# linearSensor.net
KiCad netlist of a schematic drawn in EAGLE
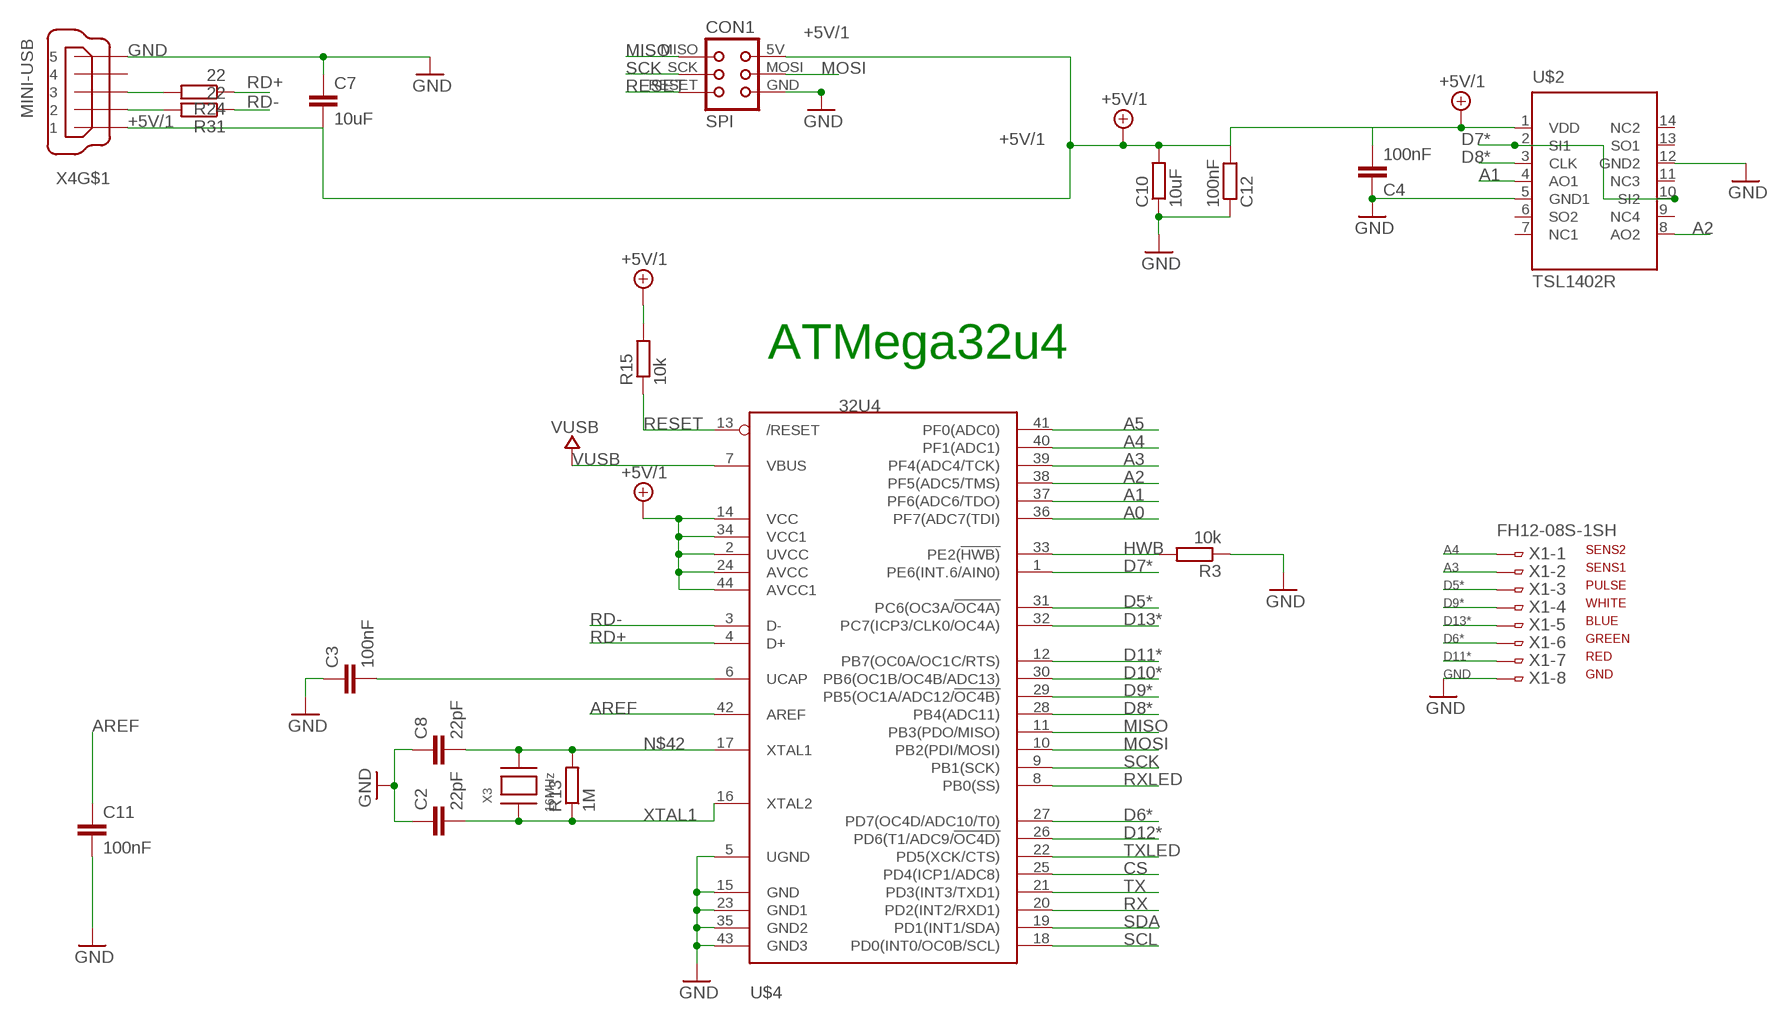
[diagram p0: schematic, sheet 1]

(export (version "E")
  (design (tool "Eeschema 10.0.6"))
  (components
    (comp (ref "C2")
      (value "22pF")
      (footprint "eagle-import:C0805K")
      (libsource (lib "eagle-import") (part "C-EUC0805K"))
    )
    (comp (ref "C3")
      (value "100nF")
      (footprint "eagle-import:C0805K")
      (libsource (lib "eagle-import") (part "C-EUC0805K"))
    )
    (comp (ref "C4")
      (value "100nF")
      (footprint "eagle-import:C0805")
      (libsource (lib "eagle-import") (part "C-EUC0805"))
    )
    (comp (ref "C7")
      (value "10uF")
      (footprint "eagle-import:C0805")
      (libsource (lib "eagle-import") (part "C-EUC0805"))
    )
    (comp (ref "C8")
      (value "22pF")
      (footprint "eagle-import:C0805K")
      (libsource (lib "eagle-import") (part "C-EUC0805K"))
    )
    (comp (ref "C10")
      (value "10uF")
      (footprint "eagle-import:M0805")
      (libsource (lib "eagle-import") (part "R-EU_M0805"))
    )
    (comp (ref "C11")
      (value "100nF")
      (footprint "eagle-import:C0805K")
      (libsource (lib "eagle-import") (part "C-EUC0805K"))
    )
    (comp (ref "C12")
      (value "100nF")
      (footprint "eagle-import:M0805")
      (libsource (lib "eagle-import") (part "R-EU_M0805"))
    )
    (comp (ref "CON1")
      (value "SPI")
      (footprint "eagle-import:TC2030-MCP-NL")
      (libsource (lib "eagle-import") (part "TINYISPT"))
    )
    (comp (ref "R3")
      (value "10k")
      (footprint "eagle-import:M0805")
      (libsource (lib "eagle-import") (part "resistor_R-EU_M0805"))
    )
    (comp (ref "R13")
      (value "1M")
      (footprint "eagle-import:M0805")
      (libsource (lib "eagle-import") (part "R-EU_M0805"))
    )
    (comp (ref "R15")
      (value "10k")
      (footprint "eagle-import:M0805")
      (libsource (lib "eagle-import") (part "resistor_R-EU_M0805"))
    )
    (comp (ref "R24")
      (value "22")
      (footprint "eagle-import:M0805")
      (libsource (lib "eagle-import") (part "R-EU_M0805"))
    )
    (comp (ref "R31")
      (value "22")
      (footprint "eagle-import:M0805")
      (libsource (lib "eagle-import") (part "R-EU_M0805"))
    )
    (comp (ref "U$2")
      (value "TSL1402R")
      (footprint "eagle-import:DIL14")
      (libsource (lib "eagle-import") (part "TSL1402R"))
    )
    (comp (ref "U$4")
      (value "32U4")
      (footprint "eagle-import:TQFP44")
      (libsource (lib "eagle-import") (part "ATMEGA32U4-AU"))
    )
    (comp (ref "X1")
      (value "FH12-08S-1SH")
      (footprint "eagle-import:FH12-08S-1SH")
      (libsource (lib "eagle-import") (part "FH12-08S-1SH"))
    )
    (comp (ref "X3")
      (value "16MHz")
      (footprint "eagle-import:NX6035")
      (libsource (lib "eagle-import") (part "XTALNX6035"))
    )
    (comp (ref "X4")
      (value "MINI-USB")
      (footprint "eagle-import:32005-201")
      (libsource (lib "eagle-import") (part "MINI-USB-SCHIELD-32005-201"))
    )
  )
  (nets
    (net (code "1") (name "+5V{slash}1") (class "Default")
      (node (ref "C10") (pin "2") (pinfunction "2_2") (pintype "passive"))
      (node (ref "C12") (pin "2") (pinfunction "2_2") (pintype "passive"))
      (node (ref "C4") (pin "2") (pinfunction "2_2") (pintype "passive"))
      (node (ref "C7") (pin "2") (pinfunction "2_2") (pintype "passive"))
      (node (ref "CON1") (pin "5V") (pinfunction "VCC_5V") (pintype "passive"))
      (node (ref "R15") (pin "2") (pinfunction "2_2") (pintype "passive"))
      (node (ref "U$2") (pin "1") (pinfunction "VDD_1") (pintype "power_in"))
      (node (ref "U$4") (pin "14") (pinfunction "VCC_14") (pintype "bidirectional"))
      (node (ref "U$4") (pin "2") (pinfunction "UVCC_2") (pintype "bidirectional"))
      (node (ref "U$4") (pin "24") (pinfunction "AVCC_24") (pintype "bidirectional"))
      (node (ref "U$4") (pin "34") (pinfunction "VCC1_34") (pintype "bidirectional"))
      (node (ref "U$4") (pin "44") (pinfunction "AVCC1_44") (pintype "bidirectional"))
      (node (ref "X4") (pin "1") (pinfunction "1_1") (pintype "passive"))
    )
    (net (code "2") (name "/A0") (class "Default")
      (node (ref "U$4") (pin "36") (pinfunction "PF7(ADC7(TDI)_36") (pintype "bidirectional"))
    )
    (net (code "3") (name "/A1") (class "Default")
      (node (ref "U$2") (pin "4") (pinfunction "AO1_4") (pintype "output"))
      (node (ref "U$4") (pin "37") (pinfunction "PF6(ADC6/TDO)_37") (pintype "bidirectional"))
    )
    (net (code "4") (name "/A2") (class "Default")
      (node (ref "U$2") (pin "8") (pinfunction "AO2_8") (pintype "output"))
      (node (ref "U$4") (pin "38") (pinfunction "PF5(ADC5/TMS)_38") (pintype "bidirectional"))
    )
    (net (code "5") (name "/A3") (class "Default")
      (node (ref "U$4") (pin "39") (pinfunction "PF4(ADC4/TCK)_39") (pintype "bidirectional"))
      (node (ref "X1") (pin "2") (pinfunction "1_2") (pintype "passive"))
    )
    (net (code "6") (name "/A4") (class "Default")
      (node (ref "U$4") (pin "40") (pinfunction "PF1(ADC1)_40") (pintype "bidirectional"))
      (node (ref "X1") (pin "1") (pinfunction "1_1") (pintype "passive"))
    )
    (net (code "7") (name "/A5") (class "Default")
      (node (ref "U$4") (pin "41") (pinfunction "PF0(ADC0)_41") (pintype "bidirectional"))
    )
    (net (code "8") (name "/AREF") (class "Default")
      (node (ref "C11") (pin "1") (pinfunction "1_1") (pintype "passive"))
      (node (ref "U$4") (pin "42") (pinfunction "AREF_42") (pintype "bidirectional"))
    )
    (net (code "9") (name "/CS") (class "Default")
      (node (ref "U$4") (pin "25") (pinfunction "PD4(ICP1/ADC8)_25") (pintype "bidirectional"))
    )
    (net (code "10") (name "/D5*") (class "Default")
      (node (ref "U$4") (pin "31") (pinfunction "PC6(OC3A/~{OC4A})_31") (pintype "bidirectional"))
      (node (ref "X1") (pin "3") (pinfunction "1_3") (pintype "passive"))
    )
    (net (code "11") (name "/D6*") (class "Default")
      (node (ref "U$4") (pin "27") (pinfunction "PD7(OC4D/ADC10/T0)_27") (pintype "bidirectional"))
      (node (ref "X1") (pin "6") (pinfunction "1_6") (pintype "passive"))
    )
    (net (code "12") (name "/D7*") (class "Default")
      (node (ref "U$2") (pin "10") (pinfunction "SI2_10") (pintype "input"))
      (node (ref "U$2") (pin "2") (pinfunction "SI1_2") (pintype "input"))
      (node (ref "U$4") (pin "1") (pinfunction "PE6(INT.6/AIN0)_1") (pintype "bidirectional"))
    )
    (net (code "13") (name "/D8*") (class "Default")
      (node (ref "U$2") (pin "3") (pinfunction "CLK_3") (pintype "input"))
      (node (ref "U$4") (pin "28") (pinfunction "PB4(ADC11)_28") (pintype "bidirectional"))
    )
    (net (code "14") (name "/D9*") (class "Default")
      (node (ref "U$4") (pin "29") (pinfunction "PB5(OC1A/ADC12/~{OC4B})_29") (pintype "bidirectional"))
      (node (ref "X1") (pin "4") (pinfunction "1_4") (pintype "passive"))
    )
    (net (code "15") (name "/D10*") (class "Default")
      (node (ref "U$4") (pin "30") (pinfunction "PB6(OC1B/OC4B/ADC13)_30") (pintype "bidirectional"))
    )
    (net (code "16") (name "/D11*") (class "Default")
      (node (ref "U$4") (pin "12") (pinfunction "PB7(OC0A/OC1C/RTS)_12") (pintype "bidirectional"))
      (node (ref "X1") (pin "7") (pinfunction "1_7") (pintype "passive"))
    )
    (net (code "17") (name "/D12*") (class "Default")
      (node (ref "U$4") (pin "26") (pinfunction "PD6(T1/ADC9/~{OC4D})_26") (pintype "bidirectional"))
    )
    (net (code "18") (name "/D13*") (class "Default")
      (node (ref "U$4") (pin "32") (pinfunction "PC7(ICP3/CLK0/OC4A)_32") (pintype "bidirectional"))
      (node (ref "X1") (pin "5") (pinfunction "1_5") (pintype "passive"))
    )
    (net (code "19") (name "/HWB") (class "Default")
      (node (ref "R3") (pin "2") (pinfunction "2_2") (pintype "passive"))
      (node (ref "U$4") (pin "33") (pinfunction "PE2(~{HWB})_33") (pintype "bidirectional"))
    )
    (net (code "20") (name "/MISO") (class "Default")
      (node (ref "CON1") (pin "MISO") (pinfunction "MISO_MISO") (pintype "passive"))
      (node (ref "U$4") (pin "11") (pinfunction "PB3(PDO/MISO)_11") (pintype "bidirectional"))
    )
    (net (code "21") (name "/MOSI") (class "Default")
      (node (ref "CON1") (pin "MOSI") (pinfunction "MOSI_MOSI") (pintype "passive"))
      (node (ref "U$4") (pin "10") (pinfunction "PB2(PDI/MOSI)_10") (pintype "bidirectional"))
    )
    (net (code "22") (name "/N$42") (class "Default")
      (node (ref "C8") (pin "2") (pinfunction "2_2") (pintype "passive"))
      (node (ref "R13") (pin "2") (pinfunction "2_2") (pintype "passive"))
      (node (ref "U$4") (pin "17") (pinfunction "XTAL1_17") (pintype "bidirectional"))
      (node (ref "X3") (pin "P$2") (pinfunction "P$2_P$2") (pintype "bidirectional"))
    )
    (net (code "23") (name "/RD+") (class "Default")
      (node (ref "R24") (pin "1") (pinfunction "1_1") (pintype "passive"))
      (node (ref "U$4") (pin "4") (pinfunction "D+_4") (pintype "bidirectional"))
    )
    (net (code "24") (name "/RD-") (class "Default")
      (node (ref "R31") (pin "1") (pinfunction "1_1") (pintype "passive"))
      (node (ref "U$4") (pin "3") (pinfunction "D-_3") (pintype "bidirectional"))
    )
    (net (code "25") (name "/RESET") (class "Default")
      (node (ref "CON1") (pin "RESET") (pinfunction "RESET_RESET") (pintype "passive"))
      (node (ref "R15") (pin "1") (pinfunction "1_1") (pintype "passive"))
      (node (ref "U$4") (pin "13") (pinfunction "/RESET_13") (pintype "bidirectional"))
    )
    (net (code "26") (name "/RX") (class "Default")
      (node (ref "U$4") (pin "20") (pinfunction "PD2(INT2/RXD1)_20") (pintype "bidirectional"))
    )
    (net (code "27") (name "/RXLED") (class "Default")
      (node (ref "U$4") (pin "8") (pinfunction "PB0(SS)_8") (pintype "bidirectional"))
    )
    (net (code "28") (name "/SCK") (class "Default")
      (node (ref "CON1") (pin "SCK") (pinfunction "SCK_SCK") (pintype "passive"))
      (node (ref "U$4") (pin "9") (pinfunction "PB1(SCK)_9") (pintype "bidirectional"))
    )
    (net (code "29") (name "/SCL") (class "Default")
      (node (ref "U$4") (pin "18") (pinfunction "PD0(INT0/OC0B/SCL)_18") (pintype "bidirectional"))
    )
    (net (code "30") (name "/SDA") (class "Default")
      (node (ref "U$4") (pin "19") (pinfunction "PD1(INT1/SDA)_19") (pintype "bidirectional"))
    )
    (net (code "31") (name "/TX") (class "Default")
      (node (ref "U$4") (pin "21") (pinfunction "PD3(INT3/TXD1)_21") (pintype "bidirectional"))
    )
    (net (code "32") (name "/TXLED") (class "Default")
      (node (ref "U$4") (pin "22") (pinfunction "PD5(XCK/CTS)_22") (pintype "bidirectional"))
    )
    (net (code "33") (name "/XTAL1") (class "Default")
      (node (ref "C2") (pin "2") (pinfunction "2_2") (pintype "passive"))
      (node (ref "R13") (pin "1") (pinfunction "1_1") (pintype "passive"))
      (node (ref "U$4") (pin "16") (pinfunction "XTAL2_16") (pintype "bidirectional"))
      (node (ref "X3") (pin "P$1") (pinfunction "P$1_P$1") (pintype "bidirectional"))
    )
    (net (code "34") (name "GND") (class "Default")
      (node (ref "C10") (pin "1") (pinfunction "1_1") (pintype "passive"))
      (node (ref "C11") (pin "2") (pinfunction "2_2") (pintype "passive"))
      (node (ref "C12") (pin "1") (pinfunction "1_1") (pintype "passive"))
      (node (ref "C2") (pin "1") (pinfunction "1_1") (pintype "passive"))
      (node (ref "C3") (pin "1") (pinfunction "1_1") (pintype "passive"))
      (node (ref "C4") (pin "1") (pinfunction "1_1") (pintype "passive"))
      (node (ref "C7") (pin "1") (pinfunction "1_1") (pintype "passive"))
      (node (ref "C8") (pin "1") (pinfunction "1_1") (pintype "passive"))
      (node (ref "CON1") (pin "GND") (pinfunction "GND_GND") (pintype "passive"))
      (node (ref "R3") (pin "1") (pinfunction "1_1") (pintype "passive"))
      (node (ref "U$2") (pin "12") (pinfunction "GND2_12") (pintype "power_in"))
      (node (ref "U$2") (pin "5") (pinfunction "GND1_5") (pintype "power_in"))
      (node (ref "U$4") (pin "15") (pinfunction "GND_15") (pintype "bidirectional"))
      (node (ref "U$4") (pin "23") (pinfunction "GND1_23") (pintype "bidirectional"))
      (node (ref "U$4") (pin "35") (pinfunction "GND2_35") (pintype "bidirectional"))
      (node (ref "U$4") (pin "43") (pinfunction "GND3_43") (pintype "bidirectional"))
      (node (ref "U$4") (pin "5") (pinfunction "UGND_5") (pintype "bidirectional"))
      (node (ref "X1") (pin "8") (pinfunction "1_8") (pintype "passive"))
      (node (ref "X4") (pin "5") (pinfunction "5_5") (pintype "passive"))
    )
    (net (code "35") (name "Net-(R24-Pad2)") (class "Default")
      (node (ref "R24") (pin "2") (pinfunction "2_2") (pintype "passive"))
      (node (ref "X4") (pin "3") (pinfunction "3_3") (pintype "passive"))
    )
    (net (code "36") (name "Net-(R31-Pad2)") (class "Default")
      (node (ref "R31") (pin "2") (pinfunction "2_2") (pintype "passive"))
      (node (ref "X4") (pin "2") (pinfunction "2_2") (pintype "passive"))
    )
    (net (code "37") (name "Net-(U$4-UCAP)") (class "Default")
      (node (ref "C3") (pin "2") (pinfunction "2_2") (pintype "passive"))
      (node (ref "U$4") (pin "6") (pinfunction "UCAP_6") (pintype "bidirectional"))
    )
    (net (code "38") (name "VUSB") (class "Default")
      (node (ref "U$4") (pin "7") (pinfunction "VBUS_7") (pintype "bidirectional"))
    )
    (net (code "39") (name "unconnected-(U$2-NC1-Pad7)") (class "Default")
      (node (ref "U$2") (pin "7") (pinfunction "NC1_7") (pintype "no_connect"))
    )
    (net (code "40") (name "unconnected-(U$2-NC2-Pad14)") (class "Default")
      (node (ref "U$2") (pin "14") (pinfunction "NC2_14") (pintype "no_connect"))
    )
    (net (code "41") (name "unconnected-(U$2-NC3-Pad11)") (class "Default")
      (node (ref "U$2") (pin "11") (pinfunction "NC3_11") (pintype "no_connect"))
    )
    (net (code "42") (name "unconnected-(U$2-NC4-Pad9)") (class "Default")
      (node (ref "U$2") (pin "9") (pinfunction "NC4_9") (pintype "no_connect"))
    )
    (net (code "43") (name "unconnected-(U$2-SO1-Pad13)") (class "Default")
      (node (ref "U$2") (pin "13") (pinfunction "SO1_13") (pintype "output"))
    )
    (net (code "44") (name "unconnected-(U$2-SO2-Pad6)") (class "Default")
      (node (ref "U$2") (pin "6") (pinfunction "SO2_6") (pintype "output"))
    )
    (net (code "45") (name "unconnected-(X4-Pad4)") (class "Default")
      (node (ref "X4") (pin "4") (pinfunction "4_4") (pintype "passive"))
    )
  )
)
